# TAG_connect-iso.net
KiCad netlist of a schematic drawn in EAGLE
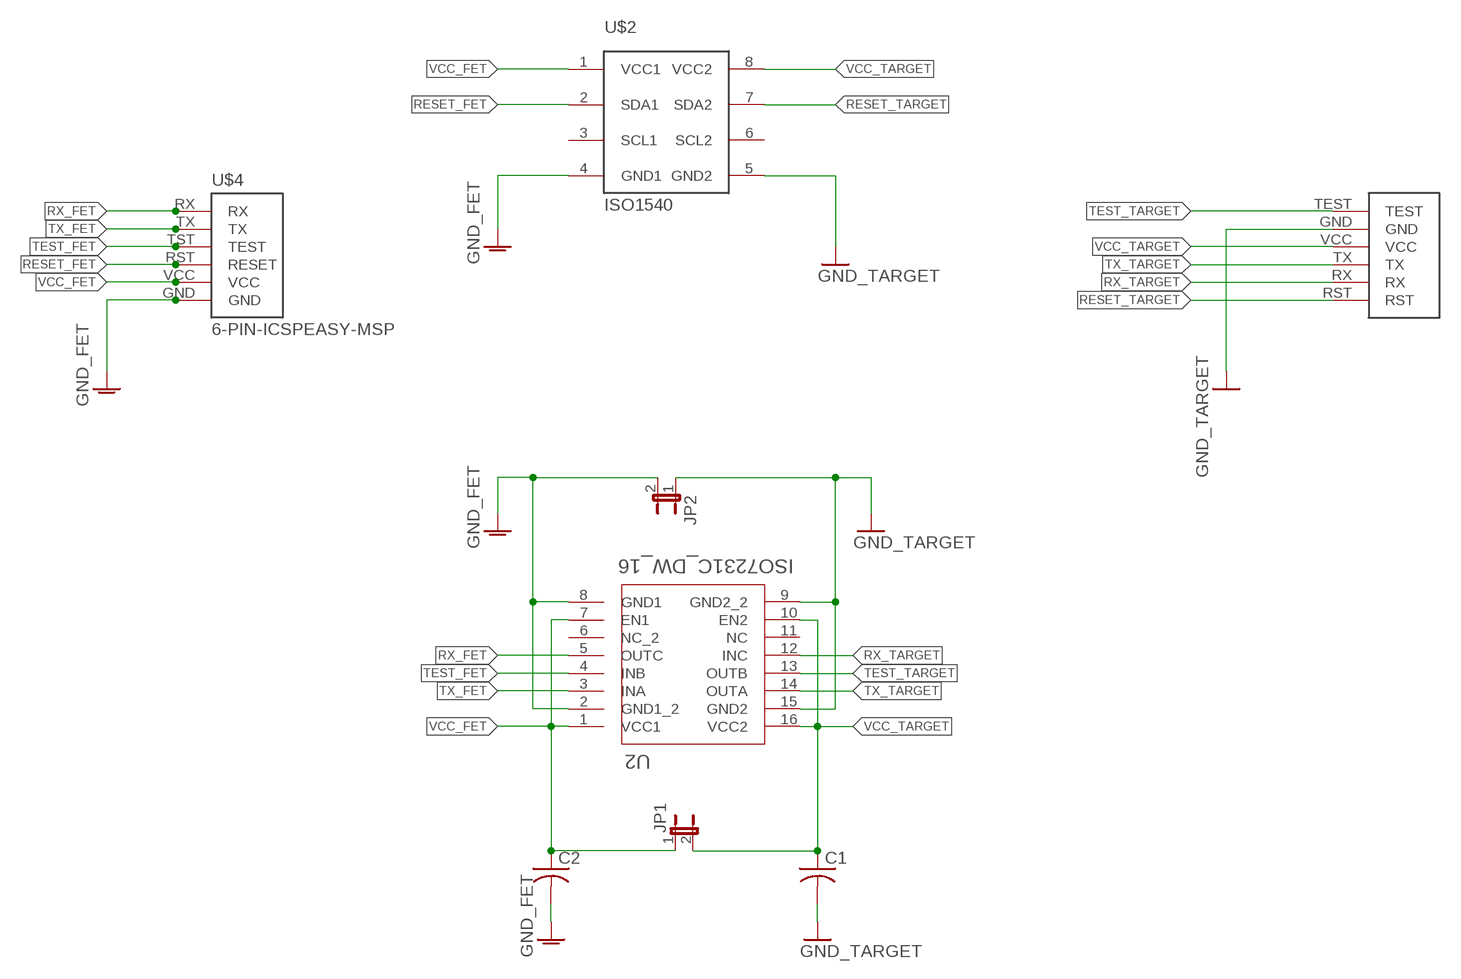
[diagram p0: schematic, sheet 1]

(export (version "E")
  (design (tool "Eeschema 10.0.6"))
  (components
    (comp (ref "C1")
      (value "C-USC1206")
      (footprint "eagle-import:C1206")
      (libsource (lib "eagle-import") (part "C-USC1206"))
    )
    (comp (ref "C2")
      (value "C-USC1206")
      (footprint "eagle-import:C1206")
      (libsource (lib "eagle-import") (part "C-USC1206"))
    )
    (comp (ref "JP1")
      (value "JUMPER-2PTH_LOCK")
      (footprint "eagle-import:1X02_LOCK")
      (libsource (lib "eagle-import") (part "JUMPER-2PTH_LOCK"))
    )
    (comp (ref "JP2")
      (value "JUMPER-2PTH_LOCK")
      (footprint "eagle-import:1X02_LOCK")
      (libsource (lib "eagle-import") (part "JUMPER-2PTH_LOCK"))
    )
    (comp (ref "U$1")
      (value "RJ-12SMD")
      (footprint "eagle-import:MOLEX_RJ45_SMD")
      (libsource (lib "eagle-import") (part "RJ-12SMD"))
    )
    (comp (ref "U$2")
      (value "ISO1540")
      (footprint "eagle-import:D8")
      (libsource (lib "eagle-import") (part "ISO1540"))
    )
    (comp (ref "U$4")
      (value "6-PIN-ICSPEASY-MSP")
      (footprint "eagle-import:EASYMSP-6PIN")
      (libsource (lib "eagle-import") (part "6-PIN-ICSPEASY-MSP"))
    )
    (comp (ref "U2")
      (value "ISO7231C_DW_16")
      (footprint "eagle-import:DW16")
      (fields
        (field (name "GENERIC_PART_NUMBER") "ISO7231C")
        (field (name "MANUFACTURER") "Texas Instruments")
        (field (name "MANUFACTURER_PART_NUMBER") "iso7231c_dw_16")
      )
      (libsource (lib "eagle-import") (part "ISO7231C_DW_16"))
    )
  )
  (nets
    (net (code "1") (name "GND_FET") (class "Default")
      (node (ref "C2") (pin "2") (pinfunction "2_2") (pintype "passive"))
      (node (ref "JP2") (pin "2") (pinfunction "2_2") (pintype "passive"))
      (node (ref "U$2") (pin "4") (pinfunction "GND1_4") (pintype "bidirectional"))
      (node (ref "U$4") (pin "GND") (pinfunction "GND_GND") (pintype "bidirectional"))
      (node (ref "U2") (pin "2") (pinfunction "GND1_2_2") (pintype "power_in"))
      (node (ref "U2") (pin "8") (pinfunction "GND1_8") (pintype "power_in"))
    )
    (net (code "2") (name "GND_TARGET") (class "Default")
      (node (ref "C1") (pin "2") (pinfunction "2_2") (pintype "passive"))
      (node (ref "JP2") (pin "1") (pinfunction "1_1") (pintype "passive"))
      (node (ref "U$1") (pin "GND") (pinfunction "GND_GND") (pintype "bidirectional"))
      (node (ref "U$2") (pin "5") (pinfunction "GND2_5") (pintype "bidirectional"))
      (node (ref "U2") (pin "15") (pinfunction "GND2_15") (pintype "power_in"))
      (node (ref "U2") (pin "9") (pinfunction "GND2_2_9") (pintype "power_in"))
    )
    (net (code "3") (name "RESET_FET") (class "Default")
      (node (ref "U$2") (pin "2") (pinfunction "SDA1_2") (pintype "bidirectional"))
      (node (ref "U$4") (pin "RST") (pinfunction "RESET_RST") (pintype "bidirectional"))
    )
    (net (code "4") (name "RESET_TARGET") (class "Default")
      (node (ref "U$1") (pin "RST") (pinfunction "RST_RST") (pintype "bidirectional"))
      (node (ref "U$2") (pin "7") (pinfunction "SDA2_7") (pintype "bidirectional"))
    )
    (net (code "5") (name "RX_FET") (class "Default")
      (node (ref "U$4") (pin "RX") (pinfunction "RX_RX") (pintype "bidirectional"))
      (node (ref "U2") (pin "5") (pinfunction "OUTC_5") (pintype "output"))
    )
    (net (code "6") (name "RX_TARGET") (class "Default")
      (node (ref "U$1") (pin "RX") (pinfunction "RX_RX") (pintype "bidirectional"))
      (node (ref "U2") (pin "12") (pinfunction "INC_12") (pintype "input"))
    )
    (net (code "7") (name "TEST_FET") (class "Default")
      (node (ref "U$4") (pin "TST") (pinfunction "TEST_TST") (pintype "bidirectional"))
      (node (ref "U2") (pin "4") (pinfunction "INB_4") (pintype "input"))
    )
    (net (code "8") (name "TEST_TARGET") (class "Default")
      (node (ref "U$1") (pin "TEST") (pinfunction "TEST_TEST") (pintype "bidirectional"))
      (node (ref "U2") (pin "13") (pinfunction "OUTB_13") (pintype "output"))
    )
    (net (code "9") (name "TX_FET") (class "Default")
      (node (ref "U$4") (pin "TX") (pinfunction "TX_TX") (pintype "bidirectional"))
      (node (ref "U2") (pin "3") (pinfunction "INA_3") (pintype "input"))
    )
    (net (code "10") (name "TX_TARGET") (class "Default")
      (node (ref "U$1") (pin "TX") (pinfunction "TX_TX") (pintype "bidirectional"))
      (node (ref "U2") (pin "14") (pinfunction "OUTA_14") (pintype "output"))
    )
    (net (code "11") (name "VCC_FET") (class "Default")
      (node (ref "C2") (pin "1") (pinfunction "1_1") (pintype "passive"))
      (node (ref "JP1") (pin "1") (pinfunction "1_1") (pintype "passive"))
      (node (ref "U$2") (pin "1") (pinfunction "VCC1_1") (pintype "bidirectional"))
      (node (ref "U$4") (pin "VCC") (pinfunction "VCC_VCC") (pintype "bidirectional"))
      (node (ref "U2") (pin "1") (pinfunction "VCC1_1") (pintype "power_in"))
      (node (ref "U2") (pin "7") (pinfunction "EN1_7") (pintype "passive"))
    )
    (net (code "12") (name "VCC_TARGET") (class "Default")
      (node (ref "C1") (pin "1") (pinfunction "1_1") (pintype "passive"))
      (node (ref "JP1") (pin "2") (pinfunction "2_2") (pintype "passive"))
      (node (ref "U$1") (pin "VCC") (pinfunction "VCC_VCC") (pintype "bidirectional"))
      (node (ref "U$2") (pin "8") (pinfunction "VCC2_8") (pintype "bidirectional"))
      (node (ref "U2") (pin "10") (pinfunction "EN2_10") (pintype "passive"))
      (node (ref "U2") (pin "16") (pinfunction "VCC2_16") (pintype "power_in"))
    )
    (net (code "13") (name "unconnected-(U$2-SCL1-Pad3)") (class "Default")
      (node (ref "U$2") (pin "3") (pinfunction "SCL1_3") (pintype "bidirectional"))
    )
    (net (code "14") (name "unconnected-(U$2-SCL2-Pad6)") (class "Default")
      (node (ref "U$2") (pin "6") (pinfunction "SCL2_6") (pintype "bidirectional"))
    )
    (net (code "15") (name "unconnected-(U2-NC-Pad11)") (class "Default")
      (node (ref "U2") (pin "11") (pinfunction "NC_11") (pintype "passive"))
    )
    (net (code "16") (name "unconnected-(U2-NC_2-Pad6)") (class "Default")
      (node (ref "U2") (pin "6") (pinfunction "NC_2_6") (pintype "passive"))
    )
  )
)
